# 4StringDriver.net
KiCad netlist of a schematic drawn in EAGLE
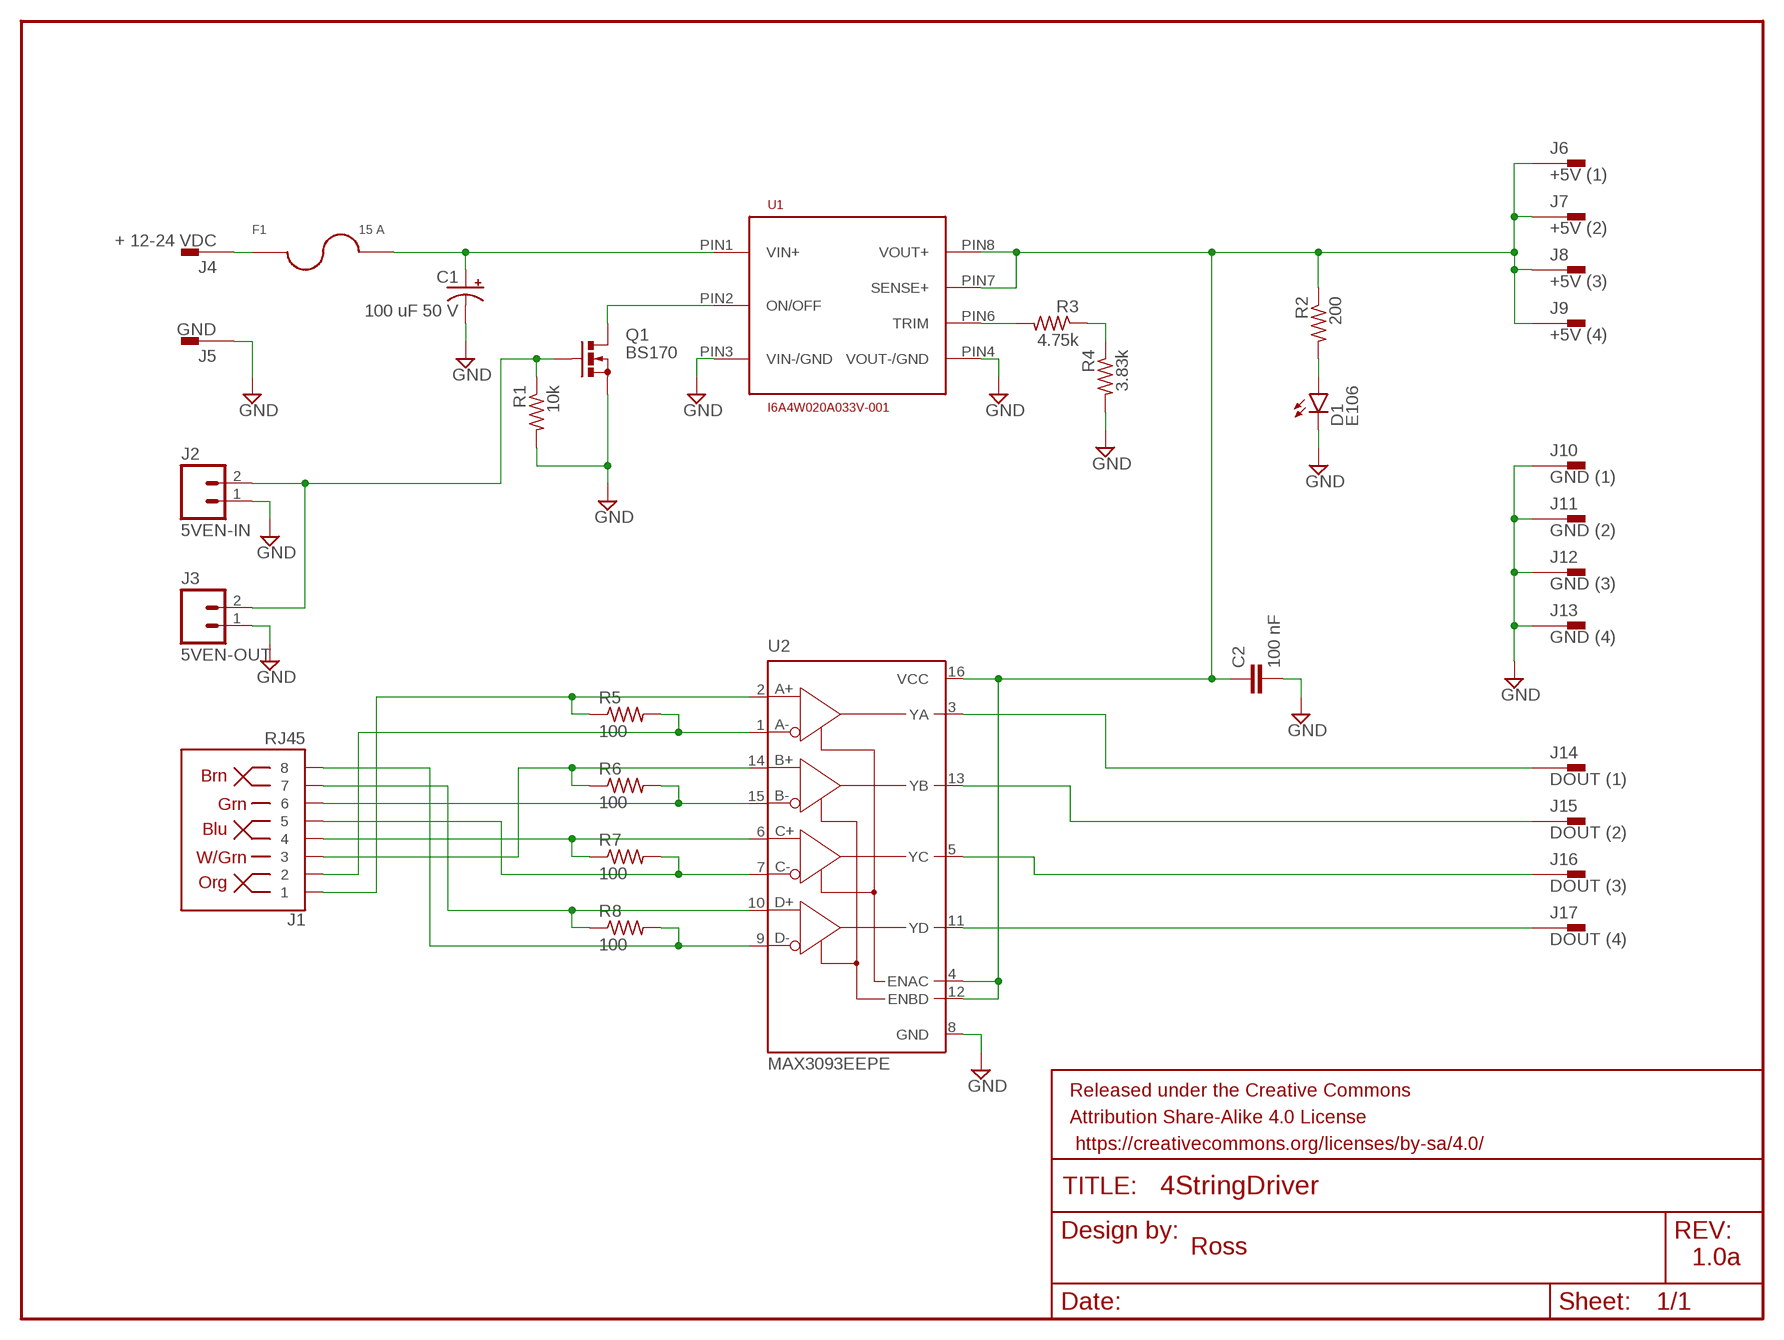
[diagram p0: schematic, sheet 1]

(export (version "E")
  (design (tool "Eeschema 10.0.6"))
  (components
    (comp (ref "C1")
      (value "100 uF 50 V")
      (footprint "eagle-import:E5-10,5")
      (libsource (lib "eagle-import") (part "CPOL-USE5-10.5"))
    )
    (comp (ref "C2")
      (value "100 nF")
      (footprint "eagle-import:CAP-PTH-SMALL-KIT")
      (libsource (lib "eagle-import") (part "0.1UF-50V-20%(PTH)KIT-EZ"))
    )
    (comp (ref "D1")
      (value "E106")
      (footprint "eagle-import:LED3MM")
      (libsource (lib "eagle-import") (part "LED3MM"))
    )
    (comp (ref "F1")
      (value "15 A")
      (footprint "eagle-import:FUSE-ATM")
      (libsource (lib "eagle-import") (part "FUSE-ATM"))
    )
    (comp (ref "FRAME1")
      (value "FRAME-LETTER")
      (footprint "eagle-import:CREATIVE_COMMONS")
      (libsource (lib "eagle-import") (part "FRAME-LETTER"))
    )
    (comp (ref "J1")
      (value "RJ45")
      (footprint "eagle-import:RJ45-8")
      (libsource (lib "eagle-import") (part "RJ45-8PTH"))
    )
    (comp (ref "J2")
      (value "5VEN-IN")
      (footprint "eagle-import:JST-2-PTH-VERT")
      (libsource (lib "eagle-import") (part "M02JST-PTH-VERT"))
    )
    (comp (ref "J3")
      (value "5VEN-OUT")
      (footprint "eagle-import:JST-2-PTH-VERT")
      (libsource (lib "eagle-import") (part "M02JST-PTH-VERT"))
    )
    (comp (ref "J4")
      (value "+ 12-24 VDC")
      (footprint "eagle-import:F061.100")
      (libsource (lib "eagle-import") (part "PIN2F061.100"))
    )
    (comp (ref "J5")
      (value "GND")
      (footprint "eagle-import:F061.100")
      (libsource (lib "eagle-import") (part "PIN2F061.100"))
    )
    (comp (ref "J6")
      (value "+5V (1)")
      (footprint "eagle-import:F061.100")
      (libsource (lib "eagle-import") (part "PIN2F061.100"))
    )
    (comp (ref "J7")
      (value "+5V (2)")
      (footprint "eagle-import:F061.100")
      (libsource (lib "eagle-import") (part "PIN2F061.100"))
    )
    (comp (ref "J8")
      (value "+5V (3)")
      (footprint "eagle-import:F061.100")
      (libsource (lib "eagle-import") (part "PIN2F061.100"))
    )
    (comp (ref "J9")
      (value "+5V (4)")
      (footprint "eagle-import:F061.100")
      (libsource (lib "eagle-import") (part "PIN2F061.100"))
    )
    (comp (ref "J10")
      (value "GND (1)")
      (footprint "eagle-import:F061.100")
      (libsource (lib "eagle-import") (part "PIN2F061.100"))
    )
    (comp (ref "J11")
      (value "GND (2)")
      (footprint "eagle-import:F061.100")
      (libsource (lib "eagle-import") (part "PIN2F061.100"))
    )
    (comp (ref "J12")
      (value "GND (3)")
      (footprint "eagle-import:F061.100")
      (libsource (lib "eagle-import") (part "PIN2F061.100"))
    )
    (comp (ref "J13")
      (value "GND (4)")
      (footprint "eagle-import:F061.100")
      (libsource (lib "eagle-import") (part "PIN2F061.100"))
    )
    (comp (ref "J14")
      (value "DOUT (1)")
      (footprint "eagle-import:F061.100")
      (libsource (lib "eagle-import") (part "PIN2F061.100"))
    )
    (comp (ref "J15")
      (value "DOUT (2)")
      (footprint "eagle-import:F061.100")
      (libsource (lib "eagle-import") (part "PIN2F061.100"))
    )
    (comp (ref "J16")
      (value "DOUT (3)")
      (footprint "eagle-import:F061.100")
      (libsource (lib "eagle-import") (part "PIN2F061.100"))
    )
    (comp (ref "J17")
      (value "DOUT (4)")
      (footprint "eagle-import:F061.100")
      (libsource (lib "eagle-import") (part "PIN2F061.100"))
    )
    (comp (ref "Q1")
      (value "BS170")
      (footprint "eagle-import:SOT54E")
      (libsource (lib "eagle-import") (part "BS170"))
    )
    (comp (ref "R1")
      (value "10k")
      (footprint "eagle-import:0204_7")
      (libsource (lib "eagle-import") (part "R-US_0204/7"))
    )
    (comp (ref "R2")
      (value "200")
      (footprint "eagle-import:0204_7")
      (libsource (lib "eagle-import") (part "R-US_0204/7"))
    )
    (comp (ref "R3")
      (value "4.75k")
      (footprint "eagle-import:0204_7")
      (libsource (lib "eagle-import") (part "R-US_0204/7"))
    )
    (comp (ref "R4")
      (value "3.83k")
      (footprint "eagle-import:0204_7")
      (libsource (lib "eagle-import") (part "R-US_0204/7"))
    )
    (comp (ref "R5")
      (value "100")
      (footprint "eagle-import:R0603")
      (libsource (lib "eagle-import") (part "R-US_R0603"))
    )
    (comp (ref "R6")
      (value "100")
      (footprint "eagle-import:R0603")
      (libsource (lib "eagle-import") (part "R-US_R0603"))
    )
    (comp (ref "R7")
      (value "100")
      (footprint "eagle-import:R0603")
      (libsource (lib "eagle-import") (part "R-US_R0603"))
    )
    (comp (ref "R8")
      (value "100")
      (footprint "eagle-import:R0603")
      (libsource (lib "eagle-import") (part "R-US_R0603"))
    )
    (comp (ref "U1")
      (value "I6A4W020A033V-001")
      (footprint "eagle-import:16TH-BRICK-POWER-MODULE-NO-OPTIONS")
      (libsource (lib "eagle-import") (part "I6A4W020A033V-001"))
    )
    (comp (ref "U2")
      (value "MAX3093EEPE")
      (footprint "eagle-import:DIL16")
      (fields (field (name "MF") "MAXIM") (field (name "MPN") "MAX3093EE+"))
      (libsource (lib "eagle-import") (part "MAX309PE3EE"))
    )
  )
  (nets
    (net (code "1") (name "GND") (class "Default")
      (node (ref "C1") (pin "-") (pinfunction "-_-") (pintype "passive"))
      (node (ref "C2") (pin "2") (pinfunction "2_2") (pintype "passive"))
      (node (ref "D1") (pin "K") (pinfunction "C_K") (pintype "passive"))
      (node (ref "J10") (pin "A1") (pinfunction "1_A1") (pintype "passive"))
      (node (ref "J10") (pin "A2") (pinfunction "1_A2") (pintype "passive"))
      (node (ref "J11") (pin "A1") (pinfunction "1_A1") (pintype "passive"))
      (node (ref "J11") (pin "A2") (pinfunction "1_A2") (pintype "passive"))
      (node (ref "J12") (pin "A1") (pinfunction "1_A1") (pintype "passive"))
      (node (ref "J12") (pin "A2") (pinfunction "1_A2") (pintype "passive"))
      (node (ref "J13") (pin "A1") (pinfunction "1_A1") (pintype "passive"))
      (node (ref "J13") (pin "A2") (pinfunction "1_A2") (pintype "passive"))
      (node (ref "J2") (pin "1") (pinfunction "1_1") (pintype "passive"))
      (node (ref "J3") (pin "1") (pinfunction "1_1") (pintype "passive"))
      (node (ref "J5") (pin "A1") (pinfunction "1_A1") (pintype "passive"))
      (node (ref "J5") (pin "A2") (pinfunction "1_A2") (pintype "passive"))
      (node (ref "Q1") (pin "S") (pinfunction "S_S") (pintype "passive"))
      (node (ref "R1") (pin "2") (pinfunction "2_2") (pintype "passive"))
      (node (ref "R4") (pin "2") (pinfunction "2_2") (pintype "passive"))
      (node (ref "U1") (pin "PIN3") (pinfunction "VIN-/GND_PIN3") (pintype "bidirectional"))
      (node (ref "U1") (pin "PIN4") (pinfunction "VOUT-/GND_PIN4") (pintype "bidirectional"))
      (node (ref "U2") (pin "8") (pinfunction "GND_8") (pintype "power_in"))
    )
    (net (code "2") (name "Net-(D1-PadA)") (class "Default")
      (node (ref "D1") (pin "A") (pinfunction "A_A") (pintype "passive"))
      (node (ref "R2") (pin "2") (pinfunction "2_2") (pintype "passive"))
    )
    (net (code "3") (name "Net-(F1-1-PadPAD1)") (class "Default")
      (node (ref "F1") (pin "PAD1") (pinfunction "1_PAD1") (pintype "bidirectional"))
      (node (ref "F1") (pin "PAD2") (pinfunction "1_PAD2") (pintype "bidirectional"))
      (node (ref "J4") (pin "A1") (pinfunction "1_A1") (pintype "passive"))
      (node (ref "J4") (pin "A2") (pinfunction "1_A2") (pintype "passive"))
    )
    (net (code "4") (name "Net-(J2-Pad2)") (class "Default")
      (node (ref "J2") (pin "2") (pinfunction "2_2") (pintype "passive"))
      (node (ref "J3") (pin "2") (pinfunction "2_2") (pintype "passive"))
      (node (ref "Q1") (pin "G") (pinfunction "G_G") (pintype "passive"))
      (node (ref "R1") (pin "1") (pinfunction "1_1") (pintype "passive"))
    )
    (net (code "5") (name "Net-(R3-Pad1)") (class "Default")
      (node (ref "R3") (pin "1") (pinfunction "1_1") (pintype "passive"))
      (node (ref "R4") (pin "1") (pinfunction "1_1") (pintype "passive"))
    )
    (net (code "6") (name "Net-(U1-ON{slash}OFF)") (class "Default")
      (node (ref "Q1") (pin "D") (pinfunction "D_D") (pintype "passive"))
      (node (ref "U1") (pin "PIN2") (pinfunction "ON/OFF_PIN2") (pintype "bidirectional"))
    )
    (net (code "7") (name "Net-(U1-SENSE+)") (class "Default")
      (node (ref "C2") (pin "1") (pinfunction "1_1") (pintype "passive"))
      (node (ref "J6") (pin "A1") (pinfunction "1_A1") (pintype "passive"))
      (node (ref "J6") (pin "A2") (pinfunction "1_A2") (pintype "passive"))
      (node (ref "J7") (pin "A1") (pinfunction "1_A1") (pintype "passive"))
      (node (ref "J7") (pin "A2") (pinfunction "1_A2") (pintype "passive"))
      (node (ref "J8") (pin "A1") (pinfunction "1_A1") (pintype "passive"))
      (node (ref "J8") (pin "A2") (pinfunction "1_A2") (pintype "passive"))
      (node (ref "J9") (pin "A1") (pinfunction "1_A1") (pintype "passive"))
      (node (ref "J9") (pin "A2") (pinfunction "1_A2") (pintype "passive"))
      (node (ref "R2") (pin "1") (pinfunction "1_1") (pintype "passive"))
      (node (ref "U1") (pin "PIN7") (pinfunction "SENSE+_PIN7") (pintype "bidirectional"))
      (node (ref "U1") (pin "PIN8") (pinfunction "VOUT+_PIN8") (pintype "bidirectional"))
      (node (ref "U2") (pin "12") (pinfunction "ENBD_12") (pintype "input"))
      (node (ref "U2") (pin "16") (pinfunction "VCC_16") (pintype "output"))
      (node (ref "U2") (pin "4") (pinfunction "ENAC_4") (pintype "input"))
    )
    (net (code "8") (name "Net-(U1-TRIM)") (class "Default")
      (node (ref "R3") (pin "2") (pinfunction "2_2") (pintype "passive"))
      (node (ref "U1") (pin "PIN6") (pinfunction "TRIM_PIN6") (pintype "bidirectional"))
    )
    (net (code "9") (name "Net-(U1-VIN+)") (class "Default")
      (node (ref "C1") (pin "+") (pinfunction "+_+") (pintype "passive"))
      (node (ref "F1") (pin "PAD3") (pinfunction "2_PAD3") (pintype "bidirectional"))
      (node (ref "F1") (pin "PAD4") (pinfunction "2_PAD4") (pintype "bidirectional"))
      (node (ref "U1") (pin "PIN1") (pinfunction "VIN+_PIN1") (pintype "bidirectional"))
    )
    (net (code "10") (name "Net-(U2-A+)") (class "Default")
      (node (ref "J1") (pin "1") (pinfunction "1_1") (pintype "bidirectional"))
      (node (ref "R5") (pin "1") (pinfunction "1_1") (pintype "passive"))
      (node (ref "U2") (pin "2") (pinfunction "A+_2") (pintype "output"))
    )
    (net (code "11") (name "Net-(U2-A-)") (class "Default")
      (node (ref "J1") (pin "2") (pinfunction "2_2") (pintype "bidirectional"))
      (node (ref "R5") (pin "2") (pinfunction "2_2") (pintype "passive"))
      (node (ref "U2") (pin "1") (pinfunction "A-_1") (pintype "output"))
    )
    (net (code "12") (name "Net-(U2-B+)") (class "Default")
      (node (ref "J1") (pin "3") (pinfunction "3_3") (pintype "bidirectional"))
      (node (ref "R6") (pin "1") (pinfunction "1_1") (pintype "passive"))
      (node (ref "U2") (pin "14") (pinfunction "B+_14") (pintype "output"))
    )
    (net (code "13") (name "Net-(U2-B-)") (class "Default")
      (node (ref "J1") (pin "6") (pinfunction "6_6") (pintype "bidirectional"))
      (node (ref "R6") (pin "2") (pinfunction "2_2") (pintype "passive"))
      (node (ref "U2") (pin "15") (pinfunction "B-_15") (pintype "output"))
    )
    (net (code "14") (name "Net-(U2-C+)") (class "Default")
      (node (ref "J1") (pin "4") (pinfunction "4_4") (pintype "bidirectional"))
      (node (ref "R7") (pin "1") (pinfunction "1_1") (pintype "passive"))
      (node (ref "U2") (pin "6") (pinfunction "C+_6") (pintype "output"))
    )
    (net (code "15") (name "Net-(U2-C-)") (class "Default")
      (node (ref "J1") (pin "5") (pinfunction "5_5") (pintype "bidirectional"))
      (node (ref "R7") (pin "2") (pinfunction "2_2") (pintype "passive"))
      (node (ref "U2") (pin "7") (pinfunction "C-_7") (pintype "output"))
    )
    (net (code "16") (name "Net-(U2-D+)") (class "Default")
      (node (ref "J1") (pin "7") (pinfunction "7_7") (pintype "bidirectional"))
      (node (ref "R8") (pin "1") (pinfunction "1_1") (pintype "passive"))
      (node (ref "U2") (pin "10") (pinfunction "D+_10") (pintype "output"))
    )
    (net (code "17") (name "Net-(U2-D-)") (class "Default")
      (node (ref "J1") (pin "8") (pinfunction "8_8") (pintype "bidirectional"))
      (node (ref "R8") (pin "2") (pinfunction "2_2") (pintype "passive"))
      (node (ref "U2") (pin "9") (pinfunction "D-_9") (pintype "output"))
    )
    (net (code "18") (name "Net-(U2-YA)") (class "Default")
      (node (ref "J14") (pin "A1") (pinfunction "1_A1") (pintype "passive"))
      (node (ref "J14") (pin "A2") (pinfunction "1_A2") (pintype "passive"))
      (node (ref "U2") (pin "3") (pinfunction "YA_3") (pintype "output"))
    )
    (net (code "19") (name "Net-(U2-YB)") (class "Default")
      (node (ref "J15") (pin "A1") (pinfunction "1_A1") (pintype "passive"))
      (node (ref "J15") (pin "A2") (pinfunction "1_A2") (pintype "passive"))
      (node (ref "U2") (pin "13") (pinfunction "YB_13") (pintype "output"))
    )
    (net (code "20") (name "Net-(U2-YC)") (class "Default")
      (node (ref "J16") (pin "A1") (pinfunction "1_A1") (pintype "passive"))
      (node (ref "J16") (pin "A2") (pinfunction "1_A2") (pintype "passive"))
      (node (ref "U2") (pin "5") (pinfunction "YC_5") (pintype "output"))
    )
    (net (code "21") (name "Net-(U2-YD)") (class "Default")
      (node (ref "J17") (pin "A1") (pinfunction "1_A1") (pintype "passive"))
      (node (ref "J17") (pin "A2") (pinfunction "1_A2") (pintype "passive"))
      (node (ref "U2") (pin "11") (pinfunction "YD_11") (pintype "output"))
    )
  )
)
